# RemoteControl.net
KiCad netlist of a schematic drawn in Altium Designer
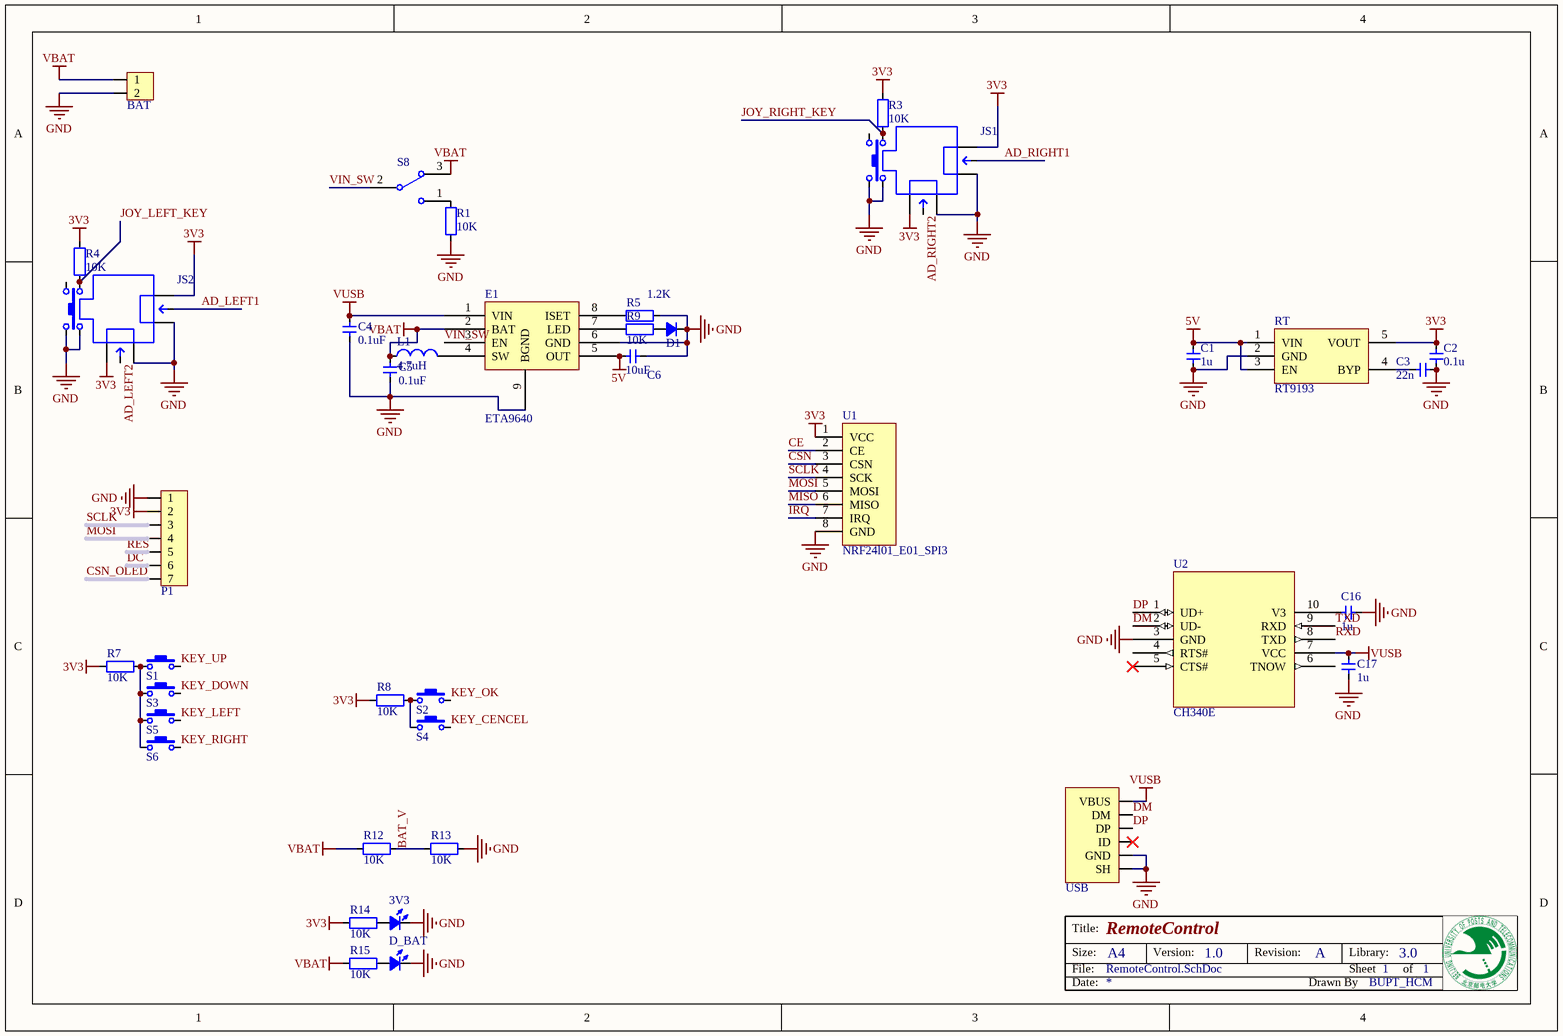
[diagram p0: RemoteControl.SchDoc]

(export (version "E")
  (design (tool "Eeschema 10.0.6"))
  (components
    (comp (ref "3V3")
      (value "LED_0805")
      (footprint "PCB_ActiveLED:LED_0805_RED")
      (description "LED")
      (libsource (lib "SCH_Active") (part "LED_0805"))
    )
    (comp (ref "BAT")
      (value "HDR1x2_2.54")
      (footprint "PCB_ConnectorHDR:HDR1X2_2.54_90")
      (description "Header")
      (libsource (lib "SCH_ConnectorHDR") (part "HDR1x2_2.54"))
    )
    (comp (ref "C1")
      (value "1u")
      (footprint "PCB_PassiveCap:CAP_0603")
      (description "Capacitor")
      (fields (field (name "Comment") "Cap_0603"))
      (libsource (lib "SCH_Passive") (part "Cap_0603"))
    )
    (comp (ref "C2")
      (value "0.1u")
      (footprint "PCB_PassiveCap:CAP_0603")
      (description "Capacitor")
      (fields (field (name "Comment") "Cap_0603"))
      (libsource (lib "SCH_Passive") (part "Cap_0603"))
    )
    (comp (ref "C3")
      (value "22n")
      (footprint "PCB_PassiveCap:CAP_0603")
      (description "Capacitor")
      (fields (field (name "Comment") "Cap_0603"))
      (libsource (lib "SCH_Passive") (part "Cap_0603"))
    )
    (comp (ref "C4")
      (value "0.1uF")
      (footprint "PCB_PassiveCap:CAP_0603")
      (description "Capacitor")
      (fields (field (name "Comment") "Cap_0603"))
      (libsource (lib "SCH_Passive") (part "Cap_0603"))
    )
    (comp (ref "C5")
      (value "0.1uF")
      (footprint "PCB_PassiveCap:CAP_0603")
      (description "Capacitor")
      (fields (field (name "Comment") "Cap_0603"))
      (libsource (lib "SCH_Passive") (part "Cap_0603"))
    )
    (comp (ref "C6")
      (value "10uF")
      (footprint "PCB_PassiveCap:CAP_0603")
      (description "Capacitor")
      (fields (field (name "Comment") "Cap_0603"))
      (libsource (lib "SCH_Passive") (part "Cap_0603"))
    )
    (comp (ref "C16")
      (value "1u")
      (footprint "PCB_PassiveCap:CAP_0603")
      (description "Capacitor")
      (fields (field (name "Comment") "Cap_0603"))
      (libsource (lib "SCH_Passive") (part "Cap_0603"))
    )
    (comp (ref "C17")
      (value "1u")
      (footprint "PCB_PassiveCap:CAP_0603")
      (description "Capacitor")
      (fields (field (name "Comment") "Cap_0603"))
      (libsource (lib "SCH_Passive") (part "Cap_0603"))
    )
    (comp (ref "D1")
      (value "D_0805")
      (footprint "LED_0805_YELLOW")
      (libsource (lib "SCH_Active") (part "D_0805"))
    )
    (comp (ref "D_BAT")
      (value "LED_0805")
      (footprint "PCB_ActiveLED:LED_0805_RED")
      (description "LED")
      (libsource (lib "SCH_Active") (part "LED_0805"))
    )
    (comp (ref "E1")
      (value "ETA9640")
      (footprint "SOP_E150_8 -with_PADs")
      (libsource (lib "SCH_IntegratedCircuit") (part "ETA9640"))
    )
    (comp (ref "JS1")
      (value "JoyStick")
      (footprint "PCB_Switch:JoyStick")
      (libsource (lib "SCH_Switch") (part "JoyStick"))
    )
    (comp (ref "JS2")
      (value "JoyStick")
      (footprint "PCB_Switch:JoyStick")
      (libsource (lib "SCH_Switch") (part "JoyStick"))
    )
    (comp (ref "L1")
      (value "4.7uH")
      (footprint "PCB_PassiveInd:IND_CD32")
      (description "Inductor")
      (fields (field (name "Comment") "Ind_CD32"))
      (libsource (lib "SCH_Passive") (part "Ind_CD32"))
    )
    (comp (ref "P1")
      (value "HDR1x7_2.54")
      (footprint "PCB_ConnectorHDR:HDR1X7_2.54_180")
      (description "Header")
      (libsource (lib "SCH_ConnectorHDR") (part "HDR1x7_2.54T"))
    )
    (comp (ref "R1")
      (value "10K")
      (footprint "PCB_PassiveRes:RES_0603")
      (description "Resistor")
      (fields (field (name "Comment") "Res_0603"))
      (libsource (lib "") (part "Res_0603_1"))
    )
    (comp (ref "R3")
      (value "10K")
      (footprint "PCB_PassiveRes:RES_0603")
      (description "Resistor")
      (fields (field (name "Comment") "Res_0603"))
      (libsource (lib "") (part "Res_0603_1"))
    )
    (comp (ref "R4")
      (value "10K")
      (footprint "PCB_PassiveRes:RES_0603")
      (description "Resistor")
      (fields (field (name "Comment") "Res_0603"))
      (libsource (lib "") (part "Res_0603_1"))
    )
    (comp (ref "R5")
      (value "1.2K")
      (footprint "PCB_PassiveRes:RES_0603")
      (description "Resistor")
      (fields (field (name "Comment") "Res_0603"))
      (libsource (lib "SCH_Passive") (part "Res_0603"))
    )
    (comp (ref "R7")
      (value "10K")
      (footprint "PCB_PassiveRes:RES_0603")
      (description "Resistor")
      (fields (field (name "Comment") "Res_0603"))
      (libsource (lib "SCH_Passive") (part "Res_0603"))
    )
    (comp (ref "R8")
      (value "10K")
      (footprint "PCB_PassiveRes:RES_0603")
      (description "Resistor")
      (fields (field (name "Comment") "Res_0603"))
      (libsource (lib "SCH_Passive") (part "Res_0603"))
    )
    (comp (ref "R9")
      (value "10K")
      (footprint "PCB_PassiveRes:RES_0603")
      (description "Resistor")
      (fields (field (name "Comment") "Res_0603"))
      (libsource (lib "SCH_Passive") (part "Res_0603"))
    )
    (comp (ref "R12")
      (value "10K")
      (footprint "PCB_PassiveRes:RES_0603")
      (description "Resistor")
      (fields (field (name "Comment") "Res_0603"))
      (libsource (lib "SCH_Passive") (part "Res_0603"))
    )
    (comp (ref "R13")
      (value "10K")
      (footprint "PCB_PassiveRes:RES_0603")
      (description "Resistor")
      (fields (field (name "Comment") "Res_0603"))
      (libsource (lib "SCH_Passive") (part "Res_0603"))
    )
    (comp (ref "R14")
      (value "10K")
      (footprint "PCB_PassiveRes:RES_0603")
      (description "Resistor")
      (fields (field (name "Comment") "Res_0603"))
      (libsource (lib "") (part "Res_0603_2"))
    )
    (comp (ref "R15")
      (value "10K")
      (footprint "PCB_PassiveRes:RES_0603")
      (description "Resistor")
      (fields (field (name "Comment") "Res_0603"))
      (libsource (lib "") (part "Res_0603_2"))
    )
    (comp (ref "RT")
      (value "RT9193")
      (footprint "PCB_IntegratedCircuit:SOT23-5")
      (description "Power")
      (libsource (lib "SCH_IntegratedCircuit") (part "RT9193"))
    )
    (comp (ref "S1")
      (value "ButtonTACT_3x6x2.5_180")
      (footprint "PCB_Switch:ButtonTACT_3x6x2.5_180")
      (description "Button")
      (libsource (lib "SCH_Switch") (part "ButtonTACT_3x6x2.5_180"))
    )
    (comp (ref "S2")
      (value "ButtonTACT_3x6x2.5_180")
      (footprint "PCB_Switch:ButtonTACT_3x6x2.5_180")
      (description "Button")
      (libsource (lib "SCH_Switch") (part "ButtonTACT_3x6x2.5_180"))
    )
    (comp (ref "S3")
      (value "ButtonTACT_3x6x2.5_180")
      (footprint "PCB_Switch:ButtonTACT_3x6x2.5_180")
      (description "Button")
      (libsource (lib "SCH_Switch") (part "ButtonTACT_3x6x2.5_180"))
    )
    (comp (ref "S4")
      (value "ButtonTACT_3x6x2.5_180")
      (footprint "PCB_Switch:ButtonTACT_3x6x2.5_180")
      (description "Button")
      (libsource (lib "SCH_Switch") (part "ButtonTACT_3x6x2.5_180"))
    )
    (comp (ref "S5")
      (value "ButtonTACT_3x6x2.5_180")
      (footprint "PCB_Switch:ButtonTACT_3x6x2.5_180")
      (description "Button")
      (libsource (lib "SCH_Switch") (part "ButtonTACT_3x6x2.5_180"))
    )
    (comp (ref "S6")
      (value "ButtonTACT_3x6x2.5_180")
      (footprint "PCB_Switch:ButtonTACT_3x6x2.5_180")
      (description "Button")
      (libsource (lib "SCH_Switch") (part "ButtonTACT_3x6x2.5_180"))
    )
    (comp (ref "S8")
      (value "SwitchSPDT_2.8x6.6_90")
      (footprint "PCB_Switch:SwitchSPDT_2.8X6.6_90")
      (description "Switch")
      (libsource (lib "SCH_Switch") (part "SwitchSPDT_2.8x6.6_90"))
    )
    (comp (ref "U1")
      (value "NRF24l01_E01_SPI3")
      (footprint "E01-ML01SP2")
      (libsource (lib "SCH_Module") (part "NRF24l01_E01_SPI2"))
    )
    (comp (ref "U2")
      (value "CH340E")
      (footprint "MSOP10")
      (description "USB to TTL Serial / UART")
      (libsource (lib "*") (part "CH340E"))
    )
    (comp (ref "USB")
      (value "USB_Micro")
      (footprint "PCB_USB:USB_Micro-AB")
      (description "USB")
      (libsource (lib "SCH_USB") (part "USB_Micro"))
    )
  )
  (nets
    (net (code "1") (name "/AD_LEFT1") (class "Default")
      (node (ref "JS2") (pin "5") (pinfunction "5_5") (pintype "passive"))
    )
    (net (code "2") (name "/AD_LEFT2") (class "Default")
      (node (ref "JS2") (pin "2") (pinfunction "2_2") (pintype "passive"))
    )
    (net (code "3") (name "/AD_RIGHT1") (class "Default")
      (node (ref "JS1") (pin "5") (pinfunction "5_5") (pintype "passive"))
    )
    (net (code "4") (name "/AD_RIGHT2") (class "Default")
      (node (ref "JS1") (pin "2") (pinfunction "2_2") (pintype "passive"))
    )
    (net (code "5") (name "/BAT_V") (class "Default")
      (node (ref "R12") (pin "1") (pinfunction "1_1") (pintype "passive"))
      (node (ref "R13") (pin "2") (pinfunction "2_2") (pintype "passive"))
    )
    (net (code "6") (name "/CE") (class "Default")
      (node (ref "U1") (pin "2") (pinfunction "CE_2") (pintype "passive"))
    )
    (net (code "7") (name "/CSN") (class "Default")
      (node (ref "U1") (pin "3") (pinfunction "CSN_3") (pintype "passive"))
    )
    (net (code "8") (name "/CSN_OLED") (class "Default")
      (node (ref "P1") (pin "7") (pinfunction "7_7") (pintype "passive"))
    )
    (net (code "9") (name "/DC") (class "Default")
      (node (ref "P1") (pin "6") (pinfunction "6_6") (pintype "passive"))
    )
    (net (code "10") (name "/DM") (class "Default")
      (node (ref "U2") (pin "2") (pinfunction "UD-_2") (pintype "bidirectional"))
      (node (ref "USB") (pin "2") (pinfunction "DM_2") (pintype "passive"))
    )
    (net (code "11") (name "/DP") (class "Default")
      (node (ref "U2") (pin "1") (pinfunction "UD+_1") (pintype "bidirectional"))
      (node (ref "USB") (pin "3") (pinfunction "DP_3") (pintype "passive"))
    )
    (net (code "12") (name "/IRQ") (class "Default")
      (node (ref "U1") (pin "7") (pinfunction "IRQ_7") (pintype "passive"))
    )
    (net (code "13") (name "/JOY_LEFT_KEY") (class "Default")
      (node (ref "JS2") (pin "9") (pinfunction "9_9") (pintype "passive"))
      (node (ref "R4") (pin "1") (pinfunction "1_1") (pintype "passive"))
    )
    (net (code "14") (name "/JOY_RIGHT_KEY") (class "Default")
      (node (ref "JS1") (pin "9") (pinfunction "9_9") (pintype "passive"))
      (node (ref "R3") (pin "1") (pinfunction "1_1") (pintype "passive"))
    )
    (net (code "15") (name "/KEY_CENCEL") (class "Default")
      (node (ref "S4") (pin "2") (pinfunction "2_2") (pintype "passive"))
    )
    (net (code "16") (name "/KEY_DOWN") (class "Default")
      (node (ref "S3") (pin "2") (pinfunction "2_2") (pintype "passive"))
    )
    (net (code "17") (name "/KEY_LEFT") (class "Default")
      (node (ref "S5") (pin "2") (pinfunction "2_2") (pintype "passive"))
    )
    (net (code "18") (name "/KEY_OK") (class "Default")
      (node (ref "S2") (pin "2") (pinfunction "2_2") (pintype "passive"))
    )
    (net (code "19") (name "/KEY_RIGHT") (class "Default")
      (node (ref "S6") (pin "2") (pinfunction "2_2") (pintype "passive"))
    )
    (net (code "20") (name "/KEY_UP") (class "Default")
      (node (ref "S1") (pin "2") (pinfunction "2_2") (pintype "passive"))
    )
    (net (code "21") (name "/MISO") (class "Default")
      (node (ref "U1") (pin "6") (pinfunction "MISO_6") (pintype "passive"))
    )
    (net (code "22") (name "/MOSI") (class "Default")
      (node (ref "P1") (pin "4") (pinfunction "4_4") (pintype "passive"))
      (node (ref "U1") (pin "5") (pinfunction "MOSI_5") (pintype "passive"))
    )
    (net (code "23") (name "/RES") (class "Default")
      (node (ref "P1") (pin "5") (pinfunction "5_5") (pintype "passive"))
    )
    (net (code "24") (name "/RXD") (class "Default")
      (node (ref "U2") (pin "8") (pinfunction "TXD_8") (pintype "output"))
    )
    (net (code "25") (name "/SCLK") (class "Default")
      (node (ref "P1") (pin "3") (pinfunction "3_3") (pintype "passive"))
      (node (ref "U1") (pin "4") (pinfunction "SCK_4") (pintype "passive"))
    )
    (net (code "26") (name "/TXD") (class "Default")
      (node (ref "U2") (pin "9") (pinfunction "RXD_9") (pintype "input"))
    )
    (net (code "27") (name "/VIN_SW") (class "Default")
      (node (ref "E1") (pin "3") (pinfunction "EN_3") (pintype "passive"))
      (node (ref "S8") (pin "2") (pinfunction "2_2") (pintype "passive"))
    )
    (net (code "28") (name "3V3") (class "Default")
      (node (ref "C2") (pin "2") (pinfunction "2_2") (pintype "passive"))
      (node (ref "JS1") (pin "1") (pinfunction "1_1") (pintype "passive"))
      (node (ref "JS1") (pin "6") (pinfunction "6_6") (pintype "passive"))
      (node (ref "JS2") (pin "1") (pinfunction "1_1") (pintype "passive"))
      (node (ref "JS2") (pin "6") (pinfunction "6_6") (pintype "passive"))
      (node (ref "P1") (pin "2") (pinfunction "2_2") (pintype "passive"))
      (node (ref "R14") (pin "1") (pinfunction "1_1") (pintype "passive"))
      (node (ref "R3") (pin "2") (pinfunction "2_2") (pintype "passive"))
      (node (ref "R4") (pin "2") (pinfunction "2_2") (pintype "passive"))
      (node (ref "R7") (pin "2") (pinfunction "2_2") (pintype "passive"))
      (node (ref "R8") (pin "2") (pinfunction "2_2") (pintype "passive"))
      (node (ref "RT") (pin "5") (pinfunction "VOUT_5") (pintype "passive"))
      (node (ref "U1") (pin "1") (pinfunction "VCC_1") (pintype "passive"))
    )
    (net (code "29") (name "5V") (class "Default")
      (node (ref "C1") (pin "2") (pinfunction "2_2") (pintype "passive"))
      (node (ref "C6") (pin "1") (pinfunction "1_1") (pintype "passive"))
      (node (ref "E1") (pin "5") (pinfunction "OUT_5") (pintype "passive"))
      (node (ref "RT") (pin "1") (pinfunction "VIN_1") (pintype "passive"))
      (node (ref "RT") (pin "3") (pinfunction "EN_3") (pintype "power_in"))
    )
    (net (code "30") (name "GND") (class "Default")
      (node (ref "3V3") (pin "2") (pinfunction "K_2") (pintype "passive"))
      (node (ref "BAT") (pin "2") (pinfunction "2_2") (pintype "passive"))
      (node (ref "C1") (pin "1") (pinfunction "1_1") (pintype "passive"))
      (node (ref "C16") (pin "1") (pinfunction "1_1") (pintype "passive"))
      (node (ref "C17") (pin "2") (pinfunction "2_2") (pintype "passive"))
      (node (ref "C2") (pin "1") (pinfunction "1_1") (pintype "passive"))
      (node (ref "C3") (pin "1") (pinfunction "1_1") (pintype "passive"))
      (node (ref "C4") (pin "2") (pinfunction "2_2") (pintype "passive"))
      (node (ref "C5") (pin "2") (pinfunction "2_2") (pintype "passive"))
      (node (ref "C6") (pin "2") (pinfunction "2_2") (pintype "passive"))
      (node (ref "D1") (pin "2") (pinfunction "K_2") (pintype "passive"))
      (node (ref "D_BAT") (pin "2") (pinfunction "K_2") (pintype "passive"))
      (node (ref "E1") (pin "6") (pinfunction "GND_6") (pintype "passive"))
      (node (ref "E1") (pin "9") (pinfunction "BGND_9") (pintype "passive"))
      (node (ref "JS1") (pin "10") (pinfunction "10_10") (pintype "passive"))
      (node (ref "JS1") (pin "3") (pinfunction "3_3") (pintype "passive"))
      (node (ref "JS1") (pin "4") (pinfunction "4_4") (pintype "passive"))
      (node (ref "JS1") (pin "8") (pinfunction "8_8") (pintype "passive"))
      (node (ref "JS2") (pin "10") (pinfunction "10_10") (pintype "passive"))
      (node (ref "JS2") (pin "3") (pinfunction "3_3") (pintype "passive"))
      (node (ref "JS2") (pin "4") (pinfunction "4_4") (pintype "passive"))
      (node (ref "JS2") (pin "8") (pinfunction "8_8") (pintype "passive"))
      (node (ref "P1") (pin "1") (pinfunction "1_1") (pintype "passive"))
      (node (ref "R1") (pin "1") (pinfunction "1_1") (pintype "passive"))
      (node (ref "R13") (pin "1") (pinfunction "1_1") (pintype "passive"))
      (node (ref "R5") (pin "1") (pinfunction "1_1") (pintype "passive"))
      (node (ref "RT") (pin "2") (pinfunction "GND_2") (pintype "passive"))
      (node (ref "U1") (pin "8") (pinfunction "GND_8") (pintype "passive"))
      (node (ref "U2") (pin "3") (pinfunction "GND_3") (pintype "power_in"))
      (node (ref "USB") (pin "0") (pinfunction "SH_0") (pintype "passive"))
      (node (ref "USB") (pin "5") (pinfunction "GND_5") (pintype "passive"))
    )
    (net (code "31") (name "Net-(3V3-A)") (class "Default")
      (node (ref "3V3") (pin "1") (pinfunction "A_1") (pintype "passive"))
      (node (ref "R14") (pin "2") (pinfunction "2_2") (pintype "passive"))
    )
    (net (code "32") (name "Net-(D1-A)") (class "Default")
      (node (ref "D1") (pin "1") (pinfunction "A_1") (pintype "passive"))
      (node (ref "R9") (pin "1") (pinfunction "1_1") (pintype "passive"))
    )
    (net (code "33") (name "Net-(D_BAT-A)") (class "Default")
      (node (ref "D_BAT") (pin "1") (pinfunction "A_1") (pintype "passive"))
      (node (ref "R15") (pin "2") (pinfunction "2_2") (pintype "passive"))
    )
    (net (code "34") (name "Net-(E1-ISET)") (class "Default")
      (node (ref "E1") (pin "8") (pinfunction "ISET_8") (pintype "passive"))
      (node (ref "R5") (pin "2") (pinfunction "2_2") (pintype "passive"))
    )
    (net (code "35") (name "Net-(E1-LED)") (class "Default")
      (node (ref "E1") (pin "7") (pinfunction "LED_7") (pintype "passive"))
      (node (ref "R9") (pin "2") (pinfunction "2_2") (pintype "passive"))
    )
    (net (code "36") (name "Net-(E1-SW)") (class "Default")
      (node (ref "E1") (pin "4") (pinfunction "SW_4") (pintype "passive"))
      (node (ref "L1") (pin "2") (pinfunction "2_2") (pintype "passive"))
    )
    (net (code "37") (name "Net-(R1-Pad2)") (class "Default")
      (node (ref "R1") (pin "2") (pinfunction "2_2") (pintype "passive"))
      (node (ref "S8") (pin "1") (pinfunction "1_1") (pintype "passive"))
    )
    (net (code "38") (name "Net-(R7-Pad1)") (class "Default")
      (node (ref "R7") (pin "1") (pinfunction "1_1") (pintype "passive"))
      (node (ref "S1") (pin "1") (pinfunction "1_1") (pintype "passive"))
      (node (ref "S3") (pin "1") (pinfunction "1_1") (pintype "passive"))
      (node (ref "S5") (pin "1") (pinfunction "1_1") (pintype "passive"))
      (node (ref "S6") (pin "1") (pinfunction "1_1") (pintype "passive"))
    )
    (net (code "39") (name "Net-(R8-Pad1)") (class "Default")
      (node (ref "R8") (pin "1") (pinfunction "1_1") (pintype "passive"))
      (node (ref "S2") (pin "1") (pinfunction "1_1") (pintype "passive"))
      (node (ref "S4") (pin "1") (pinfunction "1_1") (pintype "passive"))
    )
    (net (code "40") (name "Net-(RT-BYP)") (class "Default")
      (node (ref "C3") (pin "2") (pinfunction "2_2") (pintype "passive"))
      (node (ref "RT") (pin "4") (pinfunction "BYP_4") (pintype "passive"))
    )
    (net (code "41") (name "Net-(U2-V3)") (class "Default")
      (node (ref "C16") (pin "2") (pinfunction "2_2") (pintype "passive"))
      (node (ref "U2") (pin "10") (pinfunction "V3_10") (pintype "power_in"))
    )
    (net (code "42") (name "VBAT") (class "Default")
      (node (ref "BAT") (pin "1") (pinfunction "1_1") (pintype "passive"))
      (node (ref "C5") (pin "1") (pinfunction "1_1") (pintype "passive"))
      (node (ref "E1") (pin "2") (pinfunction "BAT_2") (pintype "passive"))
      (node (ref "L1") (pin "1") (pinfunction "1_1") (pintype "passive"))
      (node (ref "R12") (pin "2") (pinfunction "2_2") (pintype "passive"))
      (node (ref "R15") (pin "1") (pinfunction "1_1") (pintype "passive"))
      (node (ref "S8") (pin "3") (pinfunction "3_3") (pintype "passive"))
    )
    (net (code "43") (name "VUSB") (class "Default")
      (node (ref "C17") (pin "1") (pinfunction "1_1") (pintype "passive"))
      (node (ref "C4") (pin "1") (pinfunction "1_1") (pintype "passive"))
      (node (ref "E1") (pin "1") (pinfunction "VIN_1") (pintype "passive"))
      (node (ref "U2") (pin "7") (pinfunction "VCC_7") (pintype "power_in"))
      (node (ref "USB") (pin "1") (pinfunction "VBUS_1") (pintype "passive"))
    )
    (net (code "44") (name "unconnected-(JS1-Pad7)") (class "Default")
      (node (ref "JS1") (pin "7") (pinfunction "7_7") (pintype "passive"))
    )
    (net (code "45") (name "unconnected-(JS2-Pad7)") (class "Default")
      (node (ref "JS2") (pin "7") (pinfunction "7_7") (pintype "passive"))
    )
    (net (code "46") (name "unconnected-(U2-CTS#-Pad5)") (class "Default")
      (node (ref "U2") (pin "5") (pinfunction "CTS#_5") (pintype "input+no_connect"))
    )
    (net (code "47") (name "unconnected-(U2-RTS#-Pad4)") (class "Default")
      (node (ref "U2") (pin "4") (pinfunction "RTS#_4") (pintype "output"))
    )
    (net (code "48") (name "unconnected-(U2-TNOW-Pad6)") (class "Default")
      (node (ref "U2") (pin "6") (pinfunction "TNOW_6") (pintype "output"))
    )
    (net (code "49") (name "unconnected-(USB-ID-Pad4)") (class "Default")
      (node (ref "USB") (pin "4") (pinfunction "ID_4") (pintype "passive+no_connect"))
    )
  )
)
